# range_valid_stretching.net
KiCad netlist of a schematic drawn in Altium Designer
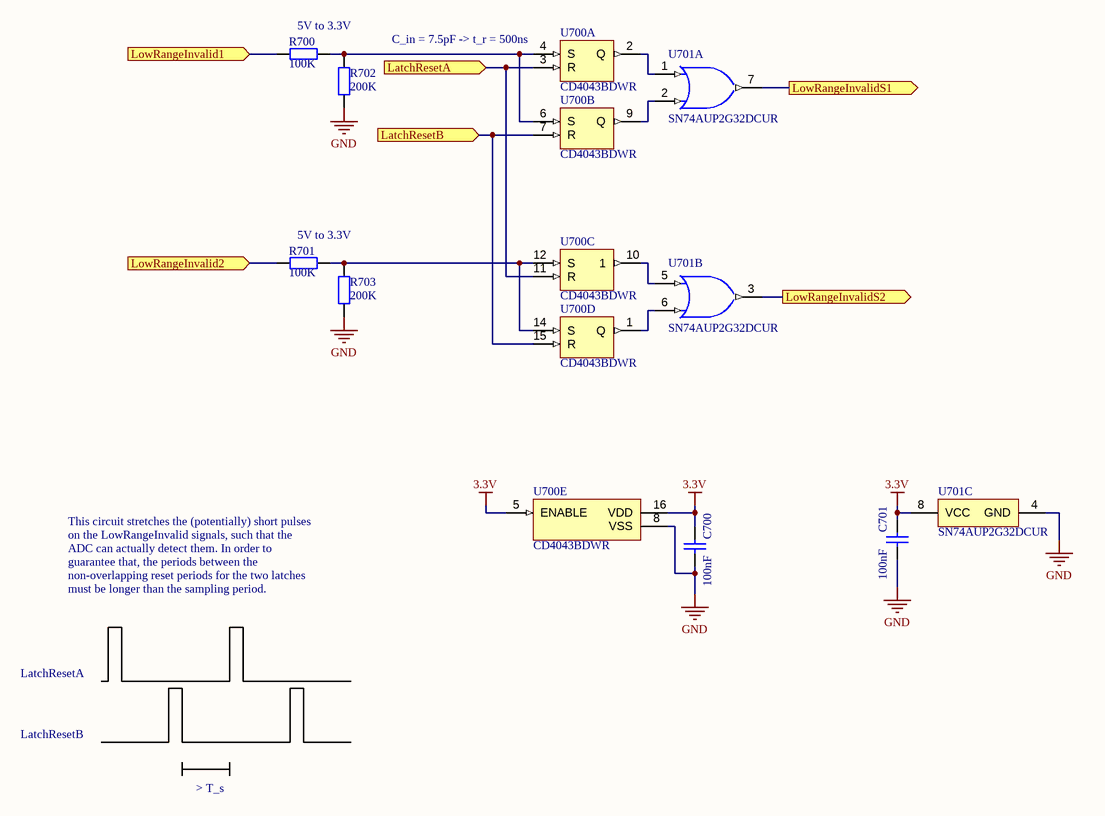
[diagram p0: range_valid_stretching.SchDoc]

(export (version "E")
  (design (tool "Eeschema 10.0.6"))
  (components
    (comp (ref "C700")
      (value "100nF")
      (footprint "CAPC0402(1005)60_L")
      (description "CAP 100nF 16V -20% to +80% 0402 (1005 Metric) Thickness 0.6mm SMD")
      (fields (field (name "TOLERANCE") "-20% to +80%"))
      (libsource (lib "Altium Content Vault") (part "CMP-1034-02071-1"))
    )
    (comp (ref "C701")
      (value "100nF")
      (footprint "CAPC0402(1005)60_L")
      (description "CAP 100nF 16V -20% to +80% 0402 (1005 Metric) Thickness 0.6mm SMD")
      (fields (field (name "TOLERANCE") "-20% to +80%"))
      (libsource (lib "Altium Content Vault") (part "CMP-1034-02071-1"))
    )
    (comp (ref "R700")
      (value "100K")
      (footprint "RESC0402(1005)_L")
      (description "100K 0.063W 5% 0402 (1005 Metric)  SMD")
      (fields (field (name "POWER") "0.063 W") (field (name "TOLERANCE") "5 %"))
      (libsource (lib "Altium Content Vault") (part "CMP-1011-00122-1"))
    )
    (comp (ref "R701")
      (value "100K")
      (footprint "RESC0402(1005)_L")
      (description "100K 0.063W 5% 0402 (1005 Metric)  SMD")
      (fields (field (name "POWER") "0.063 W") (field (name "TOLERANCE") "5 %"))
      (libsource (lib "Altium Content Vault") (part "CMP-1011-00122-1"))
    )
    (comp (ref "R702")
      (value "200K")
      (footprint "RESC0402(1005)_L")
      (description "200K 0.063W 5% 0402 (1005 Metric)  SMD")
      (fields (field (name "TOLERANCE") "5 %") (field (name "POWER") "0.063 W"))
      (libsource (lib "Altium Content Vault") (part "CMP-1011-00129-1"))
    )
    (comp (ref "R703")
      (value "200K")
      (footprint "RESC0402(1005)_L")
      (description "200K 0.063W 5% 0402 (1005 Metric)  SMD")
      (fields (field (name "TOLERANCE") "5 %") (field (name "POWER") "0.063 W"))
      (libsource (lib "Altium Content Vault") (part "CMP-1011-00129-1"))
    )
    (comp (ref "U700")
      (value "CD4043BDWR")
      (footprint "TSSOP-16_L")
      (description "IC NOR R/S LATCH 3ST QUAD 16SOIC")
      (fields (field (name "MANUFACTURER") "Texas Instruments"))
      (libsource (lib "ETHZ Vault") (part "CD4043B"))
    )
    (comp (ref "U701")
      (value "SN74AUP2G32DCUR")
      (footprint "DCU0008A_L")
      (description "Low-Power Dual 2-Input Positive-OR Gate, DCU0008A, LARGE T&R")
      (fields
        (field (name "MANUFACTURER") "Texas Instruments")
        (field (name "GENERIC PART NUMBER") "SN74AUP2G32")
      )
      (libsource (lib "Altium Content Vault") (part "TI-SN74XXX2G32-8"))
    )
  )
  (nets
    (net (code "1") (name "/LatchResetA") (class "Default")
      (node (ref "U700") (pin "11") (pinfunction "R_11") (pintype "input"))
      (node (ref "U700") (pin "3") (pinfunction "R_3") (pintype "input"))
    )
    (net (code "2") (name "/LatchResetB") (class "Default")
      (node (ref "U700") (pin "15") (pinfunction "R_15") (pintype "input"))
      (node (ref "U700") (pin "7") (pinfunction "R_7") (pintype "input"))
    )
    (net (code "3") (name "/LowRangeInvalid1") (class "Default")
      (node (ref "R700") (pin "1") (pinfunction "1_1") (pintype "passive"))
    )
    (net (code "4") (name "/LowRangeInvalid2") (class "Default")
      (node (ref "R701") (pin "1") (pinfunction "1_1") (pintype "passive"))
    )
    (net (code "5") (name "/LowRangeInvalidS1") (class "Default")
      (node (ref "U701") (pin "7") (pinfunction "1Y_7") (pintype "output"))
    )
    (net (code "6") (name "/LowRangeInvalidS2") (class "Default")
      (node (ref "U701") (pin "3") (pinfunction "2Y_3") (pintype "output"))
    )
    (net (code "7") (name "3.3V") (class "Default")
      (node (ref "C700") (pin "2") (pinfunction "2_2") (pintype "passive"))
      (node (ref "C701") (pin "2") (pinfunction "2_2") (pintype "passive"))
      (node (ref "U700") (pin "16") (pinfunction "VDD_16") (pintype "power_in"))
      (node (ref "U700") (pin "5") (pinfunction "ENABLE_5") (pintype "input"))
      (node (ref "U701") (pin "8") (pinfunction "VCC_8") (pintype "power_in"))
    )
    (net (code "8") (name "GND") (class "Default")
      (node (ref "C700") (pin "1") (pinfunction "1_1") (pintype "passive"))
      (node (ref "C701") (pin "1") (pinfunction "1_1") (pintype "passive"))
      (node (ref "R702") (pin "1") (pinfunction "1_1") (pintype "passive"))
      (node (ref "R703") (pin "1") (pinfunction "1_1") (pintype "passive"))
      (node (ref "U700") (pin "8") (pinfunction "VSS_8") (pintype "power_in"))
      (node (ref "U701") (pin "4") (pinfunction "GND_4") (pintype "power_in"))
    )
    (net (code "9") (name "Net-(U700A-Q)") (class "Default")
      (node (ref "U700") (pin "2") (pinfunction "Q_2") (pintype "output"))
      (node (ref "U701") (pin "1") (pinfunction "1A_1") (pintype "input"))
    )
    (net (code "10") (name "Net-(U700A-S)") (class "Default")
      (node (ref "R700") (pin "2") (pinfunction "2_2") (pintype "passive"))
      (node (ref "R702") (pin "2") (pinfunction "2_2") (pintype "passive"))
      (node (ref "U700") (pin "4") (pinfunction "S_4") (pintype "input"))
      (node (ref "U700") (pin "6") (pinfunction "S_6") (pintype "input"))
    )
    (net (code "11") (name "Net-(U700B-Q)") (class "Default")
      (node (ref "U700") (pin "9") (pinfunction "Q_9") (pintype "output"))
      (node (ref "U701") (pin "2") (pinfunction "1B_2") (pintype "input"))
    )
    (net (code "12") (name "Net-(U700C-1)") (class "Default")
      (node (ref "U700") (pin "10") (pinfunction "1_10") (pintype "output"))
      (node (ref "U701") (pin "5") (pinfunction "2A_5") (pintype "input"))
    )
    (net (code "13") (name "Net-(U700C-S)") (class "Default")
      (node (ref "R701") (pin "2") (pinfunction "2_2") (pintype "passive"))
      (node (ref "R703") (pin "2") (pinfunction "2_2") (pintype "passive"))
      (node (ref "U700") (pin "12") (pinfunction "S_12") (pintype "input"))
      (node (ref "U700") (pin "14") (pinfunction "S_14") (pintype "input"))
    )
    (net (code "14") (name "Net-(U700D-Q)") (class "Default")
      (node (ref "U700") (pin "1") (pinfunction "Q_1") (pintype "output"))
      (node (ref "U701") (pin "6") (pinfunction "2B_6") (pintype "input"))
    )
  )
)
